# PCB_Node_breakout.net
KiCad netlist of a schematic drawn in Altium Designer
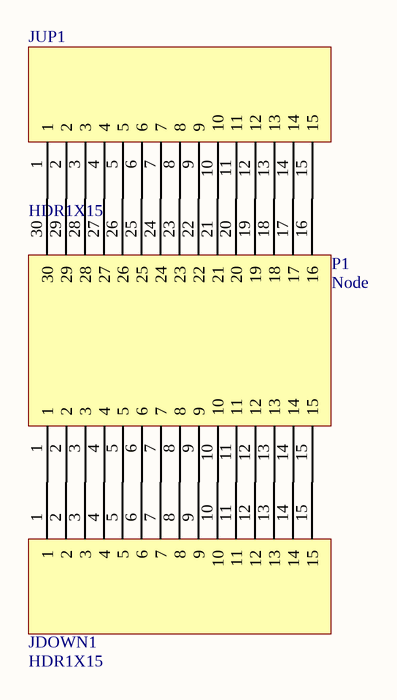
[diagram p0: PCB_Node_breakout.SchDoc]

(export (version "E")
  (design (tool "Eeschema 10.0.6"))
  (components
    (comp (ref "JDOWN1") (value "HDR1X15") (footprint "HDR1X15") (libsource (lib "") (part "HDR1X15_1")))
    (comp (ref "JUP1")
      (value "HDR1X15")
      (footprint "HDR1X15")
      (libsource (lib "PCB_Node_breakout") (part "HDR1X15"))
    )
    (comp (ref "P1")
      (value "Node")
      (footprint "NodePatten")
      (libsource (lib "PCB_Node_breakout") (part "NodePatten"))
    )
  )
  (nets
    (net (code "1") (name "Net-(JDOWN1-Pad1)") (class "Default")
      (node (ref "JDOWN1") (pin "1") (pinfunction "1_1") (pintype "passive"))
      (node (ref "P1") (pin "1") (pinfunction "1_1") (pintype "passive"))
    )
    (net (code "2") (name "Net-(JDOWN1-Pad2)") (class "Default")
      (node (ref "JDOWN1") (pin "2") (pinfunction "2_2") (pintype "passive"))
      (node (ref "P1") (pin "2") (pinfunction "2_2") (pintype "passive"))
    )
    (net (code "3") (name "Net-(JDOWN1-Pad3)") (class "Default")
      (node (ref "JDOWN1") (pin "3") (pinfunction "3_3") (pintype "passive"))
      (node (ref "P1") (pin "3") (pinfunction "3_3") (pintype "passive"))
    )
    (net (code "4") (name "Net-(JDOWN1-Pad4)") (class "Default")
      (node (ref "JDOWN1") (pin "4") (pinfunction "4_4") (pintype "passive"))
      (node (ref "P1") (pin "4") (pinfunction "4_4") (pintype "passive"))
    )
    (net (code "5") (name "Net-(JDOWN1-Pad5)") (class "Default")
      (node (ref "JDOWN1") (pin "5") (pinfunction "5_5") (pintype "passive"))
      (node (ref "P1") (pin "5") (pinfunction "5_5") (pintype "passive"))
    )
    (net (code "6") (name "Net-(JDOWN1-Pad6)") (class "Default")
      (node (ref "JDOWN1") (pin "6") (pinfunction "6_6") (pintype "passive"))
      (node (ref "P1") (pin "6") (pinfunction "6_6") (pintype "passive"))
    )
    (net (code "7") (name "Net-(JDOWN1-Pad7)") (class "Default")
      (node (ref "JDOWN1") (pin "7") (pinfunction "7_7") (pintype "passive"))
      (node (ref "P1") (pin "7") (pinfunction "7_7") (pintype "passive"))
    )
    (net (code "8") (name "Net-(JDOWN1-Pad8)") (class "Default")
      (node (ref "JDOWN1") (pin "8") (pinfunction "8_8") (pintype "passive"))
      (node (ref "P1") (pin "8") (pinfunction "8_8") (pintype "passive"))
    )
    (net (code "9") (name "Net-(JDOWN1-Pad9)") (class "Default")
      (node (ref "JDOWN1") (pin "9") (pinfunction "9_9") (pintype "passive"))
      (node (ref "P1") (pin "9") (pinfunction "9_9") (pintype "passive"))
    )
    (net (code "10") (name "Net-(JDOWN1-Pad10)") (class "Default")
      (node (ref "JDOWN1") (pin "10") (pinfunction "10_10") (pintype "passive"))
      (node (ref "P1") (pin "10") (pinfunction "10_10") (pintype "passive"))
    )
    (net (code "11") (name "Net-(JDOWN1-Pad11)") (class "Default")
      (node (ref "JDOWN1") (pin "11") (pinfunction "11_11") (pintype "passive"))
      (node (ref "P1") (pin "11") (pinfunction "11_11") (pintype "passive"))
    )
    (net (code "12") (name "Net-(JDOWN1-Pad12)") (class "Default")
      (node (ref "JDOWN1") (pin "12") (pinfunction "12_12") (pintype "passive"))
      (node (ref "P1") (pin "12") (pinfunction "12_12") (pintype "passive"))
    )
    (net (code "13") (name "Net-(JDOWN1-Pad13)") (class "Default")
      (node (ref "JDOWN1") (pin "13") (pinfunction "13_13") (pintype "passive"))
      (node (ref "P1") (pin "13") (pinfunction "13_13") (pintype "passive"))
    )
    (net (code "14") (name "Net-(JDOWN1-Pad14)") (class "Default")
      (node (ref "JDOWN1") (pin "14") (pinfunction "14_14") (pintype "passive"))
      (node (ref "P1") (pin "14") (pinfunction "14_14") (pintype "passive"))
    )
    (net (code "15") (name "Net-(JDOWN1-Pad15)") (class "Default")
      (node (ref "JDOWN1") (pin "15") (pinfunction "15_15") (pintype "passive"))
      (node (ref "P1") (pin "15") (pinfunction "15_15") (pintype "passive"))
    )
    (net (code "16") (name "Net-(JUP1-Pad1)") (class "Default")
      (node (ref "JUP1") (pin "1") (pinfunction "1_1") (pintype "passive"))
      (node (ref "P1") (pin "30") (pinfunction "30_30") (pintype "passive"))
    )
    (net (code "17") (name "Net-(JUP1-Pad2)") (class "Default")
      (node (ref "JUP1") (pin "2") (pinfunction "2_2") (pintype "passive"))
      (node (ref "P1") (pin "29") (pinfunction "29_29") (pintype "passive"))
    )
    (net (code "18") (name "Net-(JUP1-Pad3)") (class "Default")
      (node (ref "JUP1") (pin "3") (pinfunction "3_3") (pintype "passive"))
      (node (ref "P1") (pin "28") (pinfunction "28_28") (pintype "passive"))
    )
    (net (code "19") (name "Net-(JUP1-Pad4)") (class "Default")
      (node (ref "JUP1") (pin "4") (pinfunction "4_4") (pintype "passive"))
      (node (ref "P1") (pin "27") (pinfunction "27_27") (pintype "passive"))
    )
    (net (code "20") (name "Net-(JUP1-Pad5)") (class "Default")
      (node (ref "JUP1") (pin "5") (pinfunction "5_5") (pintype "passive"))
      (node (ref "P1") (pin "26") (pinfunction "26_26") (pintype "passive"))
    )
    (net (code "21") (name "Net-(JUP1-Pad6)") (class "Default")
      (node (ref "JUP1") (pin "6") (pinfunction "6_6") (pintype "passive"))
      (node (ref "P1") (pin "25") (pinfunction "25_25") (pintype "passive"))
    )
    (net (code "22") (name "Net-(JUP1-Pad7)") (class "Default")
      (node (ref "JUP1") (pin "7") (pinfunction "7_7") (pintype "passive"))
      (node (ref "P1") (pin "24") (pinfunction "24_24") (pintype "passive"))
    )
    (net (code "23") (name "Net-(JUP1-Pad8)") (class "Default")
      (node (ref "JUP1") (pin "8") (pinfunction "8_8") (pintype "passive"))
      (node (ref "P1") (pin "23") (pinfunction "23_23") (pintype "passive"))
    )
    (net (code "24") (name "Net-(JUP1-Pad9)") (class "Default")
      (node (ref "JUP1") (pin "9") (pinfunction "9_9") (pintype "passive"))
      (node (ref "P1") (pin "22") (pinfunction "22_22") (pintype "passive"))
    )
    (net (code "25") (name "Net-(JUP1-Pad10)") (class "Default")
      (node (ref "JUP1") (pin "10") (pinfunction "10_10") (pintype "passive"))
      (node (ref "P1") (pin "21") (pinfunction "21_21") (pintype "passive"))
    )
    (net (code "26") (name "Net-(JUP1-Pad11)") (class "Default")
      (node (ref "JUP1") (pin "11") (pinfunction "11_11") (pintype "passive"))
      (node (ref "P1") (pin "20") (pinfunction "20_20") (pintype "passive"))
    )
    (net (code "27") (name "Net-(JUP1-Pad12)") (class "Default")
      (node (ref "JUP1") (pin "12") (pinfunction "12_12") (pintype "passive"))
      (node (ref "P1") (pin "19") (pinfunction "19_19") (pintype "passive"))
    )
    (net (code "28") (name "Net-(JUP1-Pad13)") (class "Default")
      (node (ref "JUP1") (pin "13") (pinfunction "13_13") (pintype "passive"))
      (node (ref "P1") (pin "18") (pinfunction "18_18") (pintype "passive"))
    )
    (net (code "29") (name "Net-(JUP1-Pad14)") (class "Default")
      (node (ref "JUP1") (pin "14") (pinfunction "14_14") (pintype "passive"))
      (node (ref "P1") (pin "17") (pinfunction "17_17") (pintype "passive"))
    )
    (net (code "30") (name "Net-(JUP1-Pad15)") (class "Default")
      (node (ref "JUP1") (pin "15") (pinfunction "15_15") (pintype "passive"))
      (node (ref "P1") (pin "16") (pinfunction "16_16") (pintype "passive"))
    )
  )
)
